# MYC_Klimasensor_small.net
KiCad netlist of a schematic drawn in EAGLE
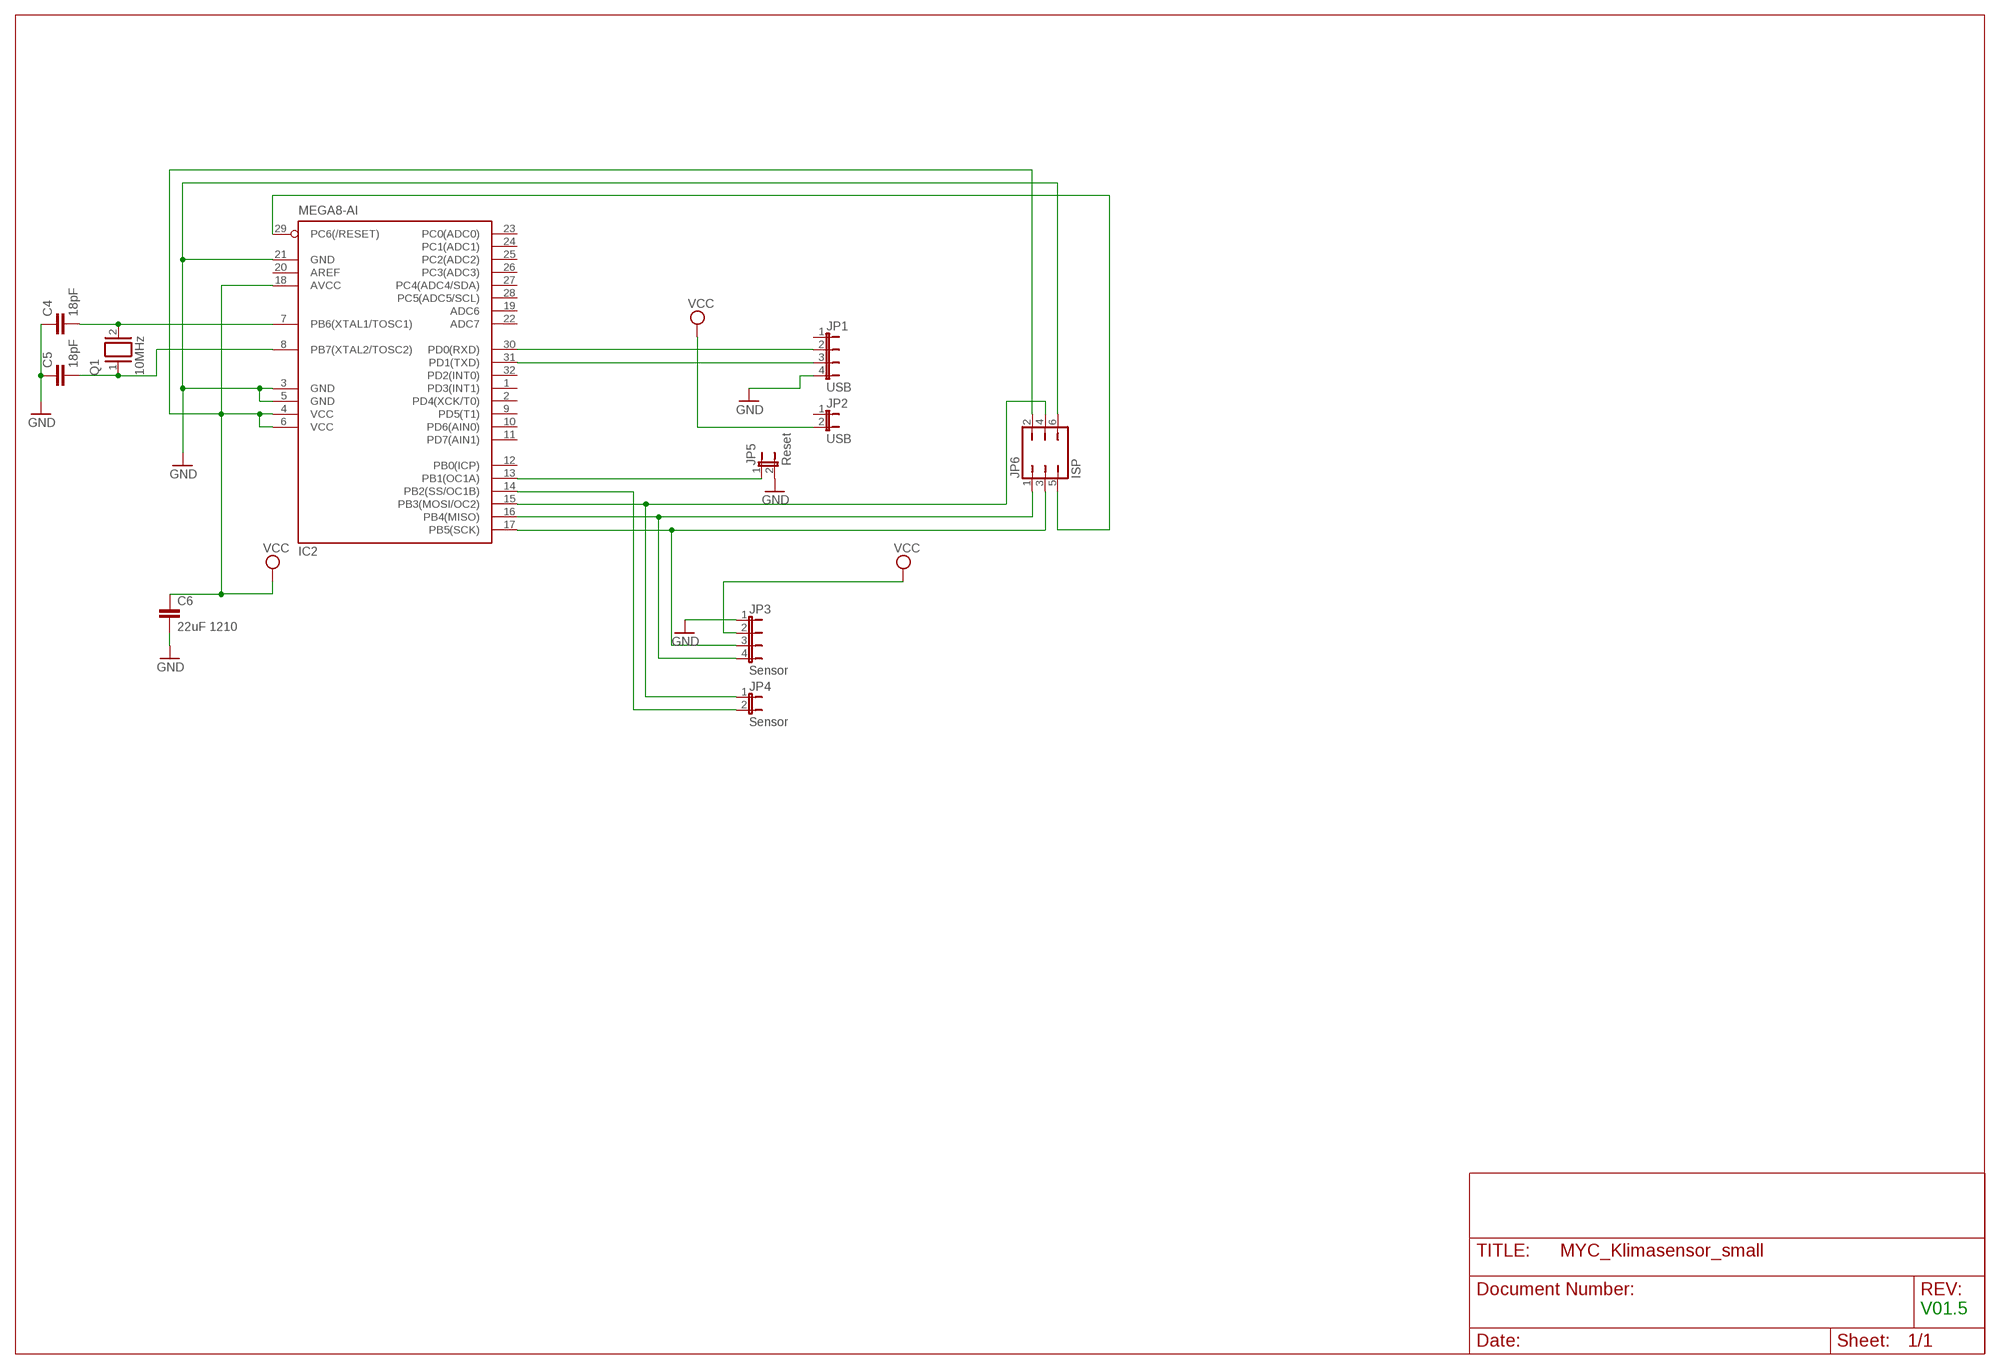
[diagram p0: schematic, sheet 1]

(export (version "E")
  (design (tool "Eeschema 10.0.6"))
  (components
    (comp (ref "C4")
      (value "18pF")
      (footprint "eagle-import:C025-025X050")
      (libsource (lib "eagle-import") (part "resistor_C-EU025-025X050"))
    )
    (comp (ref "C5")
      (value "18pF")
      (footprint "eagle-import:C025-025X050")
      (libsource (lib "eagle-import") (part "resistor_C-EU025-025X050"))
    )
    (comp (ref "C6")
      (value "22uF 1210")
      (footprint "eagle-import:C1206")
      (libsource (lib "eagle-import") (part "C-EUC1206"))
    )
    (comp (ref "IC2")
      (value "MEGA8-AI")
      (footprint "eagle-import:TQFP32-08")
      (fields (field (name "MPN") "ATMEGA8-16AU"))
      (libsource (lib "eagle-import") (part "MEGA8-AI"))
    )
    (comp (ref "JP1")
      (value "USB")
      (footprint "eagle-import:JP4")
      (libsource (lib "eagle-import") (part "JP4E"))
    )
    (comp (ref "JP2")
      (value "USB")
      (footprint "eagle-import:JP1")
      (libsource (lib "eagle-import") (part "JP1E"))
    )
    (comp (ref "JP3")
      (value "Sensor")
      (footprint "eagle-import:JP4")
      (libsource (lib "eagle-import") (part "JP4E"))
    )
    (comp (ref "JP4")
      (value "Sensor")
      (footprint "eagle-import:JP1")
      (libsource (lib "eagle-import") (part "JP1E"))
    )
    (comp (ref "JP5")
      (value "Reset")
      (footprint "eagle-import:JP1")
      (libsource (lib "eagle-import") (part "JP1E"))
    )
    (comp (ref "JP6")
      (value "ISP")
      (footprint "eagle-import:JP3Q")
      (libsource (lib "eagle-import") (part "JP3Q"))
    )
    (comp (ref "Q1")
      (value "10MHz")
      (footprint "eagle-import:QS")
      (libsource (lib "eagle-import") (part "XTAL/S"))
    )
  )
  (nets
    (net (code "1") (name "GND") (class "Default")
      (node (ref "C4") (pin "1") (pinfunction "1_1") (pintype "passive"))
      (node (ref "C5") (pin "1") (pinfunction "1_1") (pintype "passive"))
      (node (ref "C6") (pin "2") (pinfunction "2_2") (pintype "passive"))
      (node (ref "IC2") (pin "21") (pinfunction "GND_21") (pintype "power_in"))
      (node (ref "IC2") (pin "3") (pinfunction "GND_3") (pintype "power_in"))
      (node (ref "IC2") (pin "5") (pinfunction "GND_5") (pintype "power_in"))
      (node (ref "JP1") (pin "4") (pinfunction "4_4") (pintype "passive"))
      (node (ref "JP3") (pin "1") (pinfunction "1_1") (pintype "passive"))
      (node (ref "JP5") (pin "2") (pinfunction "2_2") (pintype "passive"))
      (node (ref "JP6") (pin "6") (pinfunction "6_6") (pintype "passive"))
    )
    (net (code "2") (name "Net-(IC2-PB1(OC1A))") (class "Default")
      (node (ref "IC2") (pin "13") (pinfunction "PB1(OC1A)_13") (pintype "bidirectional"))
      (node (ref "JP5") (pin "1") (pinfunction "1_1") (pintype "passive"))
    )
    (net (code "3") (name "Net-(IC2-PB2(SS{slash}OC1B))") (class "Default")
      (node (ref "IC2") (pin "14") (pinfunction "PB2(SS/OC1B)_14") (pintype "bidirectional"))
      (node (ref "JP4") (pin "2") (pinfunction "2_2") (pintype "passive"))
    )
    (net (code "4") (name "Net-(IC2-PB3(MOSI{slash}OC2))") (class "Default")
      (node (ref "IC2") (pin "15") (pinfunction "PB3(MOSI/OC2)_15") (pintype "bidirectional"))
      (node (ref "JP4") (pin "1") (pinfunction "1_1") (pintype "passive"))
      (node (ref "JP6") (pin "4") (pinfunction "4_4") (pintype "passive"))
    )
    (net (code "5") (name "Net-(IC2-PB4(MISO))") (class "Default")
      (node (ref "IC2") (pin "16") (pinfunction "PB4(MISO)_16") (pintype "bidirectional"))
      (node (ref "JP3") (pin "4") (pinfunction "4_4") (pintype "passive"))
      (node (ref "JP6") (pin "1") (pinfunction "1_1") (pintype "passive"))
    )
    (net (code "6") (name "Net-(IC2-PB5(SCK))") (class "Default")
      (node (ref "IC2") (pin "17") (pinfunction "PB5(SCK)_17") (pintype "bidirectional"))
      (node (ref "JP3") (pin "3") (pinfunction "3_3") (pintype "passive"))
      (node (ref "JP6") (pin "3") (pinfunction "3_3") (pintype "passive"))
    )
    (net (code "7") (name "Net-(IC2-PB6(XTAL1{slash}TOSC1))") (class "Default")
      (node (ref "C4") (pin "2") (pinfunction "2_2") (pintype "passive"))
      (node (ref "IC2") (pin "7") (pinfunction "PB6(XTAL1/TOSC1)_7") (pintype "bidirectional"))
      (node (ref "Q1") (pin "2") (pinfunction "2_2") (pintype "passive"))
    )
    (net (code "8") (name "Net-(IC2-PB7(XTAL2{slash}TOSC2))") (class "Default")
      (node (ref "C5") (pin "2") (pinfunction "2_2") (pintype "passive"))
      (node (ref "IC2") (pin "8") (pinfunction "PB7(XTAL2/TOSC2)_8") (pintype "bidirectional"))
      (node (ref "Q1") (pin "1") (pinfunction "1_1") (pintype "passive"))
    )
    (net (code "9") (name "Net-(IC2-PC6({slash}RESET))") (class "Default")
      (node (ref "IC2") (pin "29") (pinfunction "PC6(/RESET)_29") (pintype "bidirectional"))
      (node (ref "JP6") (pin "5") (pinfunction "5_5") (pintype "passive"))
    )
    (net (code "10") (name "Net-(IC2-PD0(RXD))") (class "Default")
      (node (ref "IC2") (pin "30") (pinfunction "PD0(RXD)_30") (pintype "bidirectional"))
      (node (ref "JP1") (pin "2") (pinfunction "2_2") (pintype "passive"))
    )
    (net (code "11") (name "Net-(IC2-PD1(TXD))") (class "Default")
      (node (ref "IC2") (pin "31") (pinfunction "PD1(TXD)_31") (pintype "bidirectional"))
      (node (ref "JP1") (pin "3") (pinfunction "3_3") (pintype "passive"))
    )
    (net (code "12") (name "VCC") (class "Default")
      (node (ref "C6") (pin "1") (pinfunction "1_1") (pintype "passive"))
      (node (ref "IC2") (pin "18") (pinfunction "AVCC_18") (pintype "power_in"))
      (node (ref "IC2") (pin "4") (pinfunction "VCC_4") (pintype "power_in"))
      (node (ref "IC2") (pin "6") (pinfunction "VCC_6") (pintype "power_in"))
      (node (ref "JP2") (pin "2") (pinfunction "2_2") (pintype "passive"))
      (node (ref "JP3") (pin "2") (pinfunction "2_2") (pintype "passive"))
      (node (ref "JP6") (pin "2") (pinfunction "2_2") (pintype "passive"))
    )
    (net (code "13") (name "unconnected-(IC2-ADC6-Pad19)") (class "Default")
      (node (ref "IC2") (pin "19") (pinfunction "ADC6_19") (pintype "bidirectional"))
    )
    (net (code "14") (name "unconnected-(IC2-ADC7-Pad22)") (class "Default")
      (node (ref "IC2") (pin "22") (pinfunction "ADC7_22") (pintype "bidirectional"))
    )
    (net (code "15") (name "unconnected-(IC2-AREF-Pad20)") (class "Default")
      (node (ref "IC2") (pin "20") (pinfunction "AREF_20") (pintype "passive"))
    )
    (net (code "16") (name "unconnected-(IC2-PB0(ICP)-Pad12)") (class "Default")
      (node (ref "IC2") (pin "12") (pinfunction "PB0(ICP)_12") (pintype "bidirectional"))
    )
    (net (code "17") (name "unconnected-(IC2-PC0(ADC0)-Pad23)") (class "Default")
      (node (ref "IC2") (pin "23") (pinfunction "PC0(ADC0)_23") (pintype "bidirectional"))
    )
    (net (code "18") (name "unconnected-(IC2-PC1(ADC1)-Pad24)") (class "Default")
      (node (ref "IC2") (pin "24") (pinfunction "PC1(ADC1)_24") (pintype "bidirectional"))
    )
    (net (code "19") (name "unconnected-(IC2-PC2(ADC2)-Pad25)") (class "Default")
      (node (ref "IC2") (pin "25") (pinfunction "PC2(ADC2)_25") (pintype "bidirectional"))
    )
    (net (code "20") (name "unconnected-(IC2-PC3(ADC3)-Pad26)") (class "Default")
      (node (ref "IC2") (pin "26") (pinfunction "PC3(ADC3)_26") (pintype "bidirectional"))
    )
    (net (code "21") (name "unconnected-(IC2-PC4(ADC4{slash}SDA)-Pad27)") (class "Default")
      (node (ref "IC2") (pin "27") (pinfunction "PC4(ADC4/SDA)_27") (pintype "bidirectional"))
    )
    (net (code "22") (name "unconnected-(IC2-PC5(ADC5{slash}SCL)-Pad28)") (class "Default")
      (node (ref "IC2") (pin "28") (pinfunction "PC5(ADC5/SCL)_28") (pintype "bidirectional"))
    )
    (net (code "23") (name "unconnected-(IC2-PD2(INT0)-Pad32)") (class "Default")
      (node (ref "IC2") (pin "32") (pinfunction "PD2(INT0)_32") (pintype "bidirectional"))
    )
    (net (code "24") (name "unconnected-(IC2-PD3(INT1)-Pad1)") (class "Default")
      (node (ref "IC2") (pin "1") (pinfunction "PD3(INT1)_1") (pintype "bidirectional"))
    )
    (net (code "25") (name "unconnected-(IC2-PD4(XCK{slash}T0)-Pad2)") (class "Default")
      (node (ref "IC2") (pin "2") (pinfunction "PD4(XCK/T0)_2") (pintype "bidirectional"))
    )
    (net (code "26") (name "unconnected-(IC2-PD5(T1)-Pad9)") (class "Default")
      (node (ref "IC2") (pin "9") (pinfunction "PD5(T1)_9") (pintype "bidirectional"))
    )
    (net (code "27") (name "unconnected-(IC2-PD6(AIN0)-Pad10)") (class "Default")
      (node (ref "IC2") (pin "10") (pinfunction "PD6(AIN0)_10") (pintype "bidirectional"))
    )
    (net (code "28") (name "unconnected-(IC2-PD7(AIN1)-Pad11)") (class "Default")
      (node (ref "IC2") (pin "11") (pinfunction "PD7(AIN1)_11") (pintype "bidirectional"))
    )
    (net (code "29") (name "unconnected-(JP1-Pad1)") (class "Default")
      (node (ref "JP1") (pin "1") (pinfunction "1_1") (pintype "passive"))
    )
    (net (code "30") (name "unconnected-(JP2-Pad1)") (class "Default")
      (node (ref "JP2") (pin "1") (pinfunction "1_1") (pintype "passive"))
    )
  )
)
